# ioboard.net
KiCad netlist of a schematic drawn in EAGLE
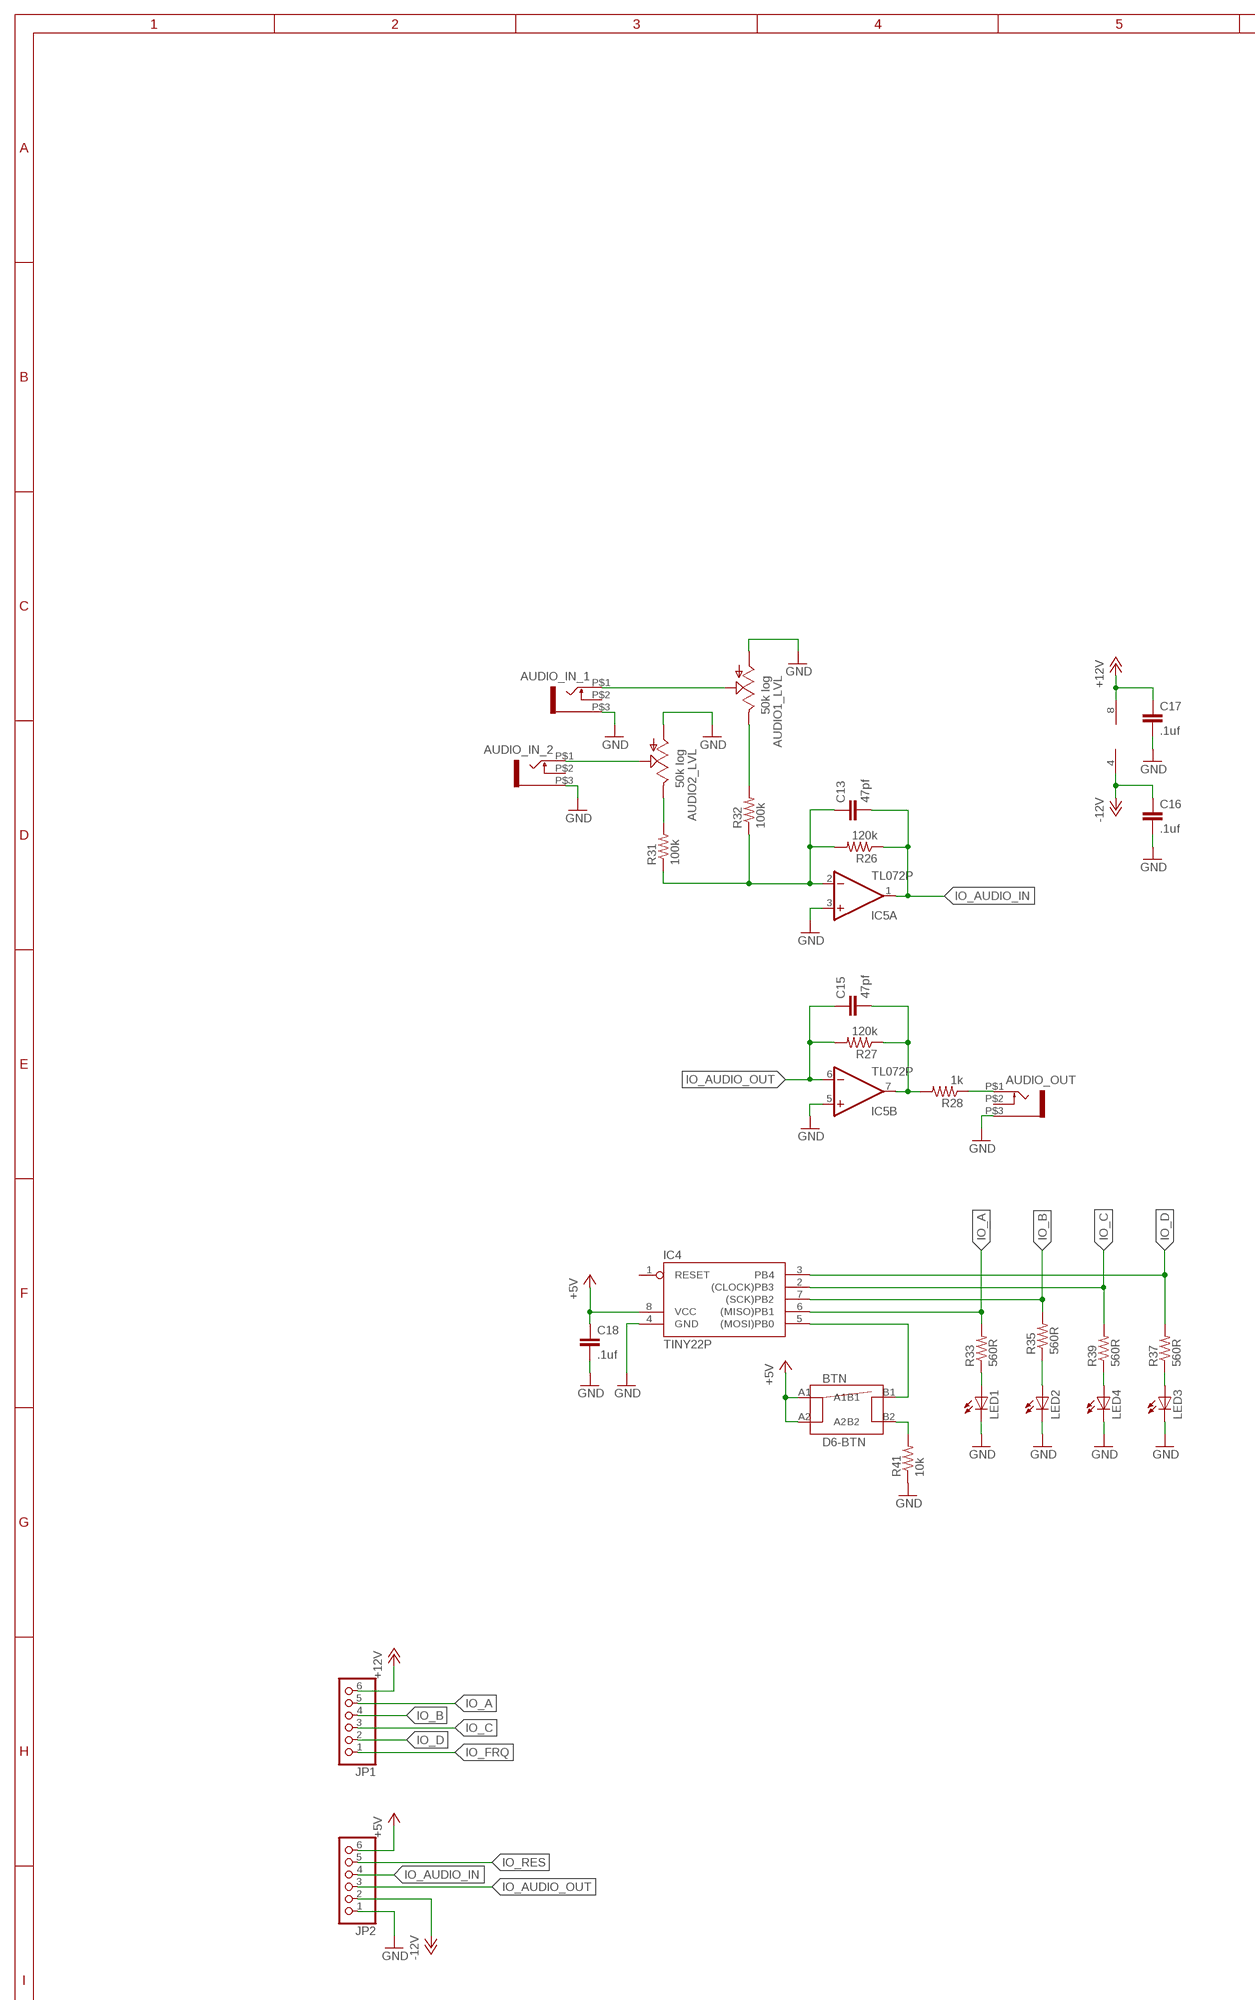
[diagram p0: schematic, sheet 1, part 1 of 2]
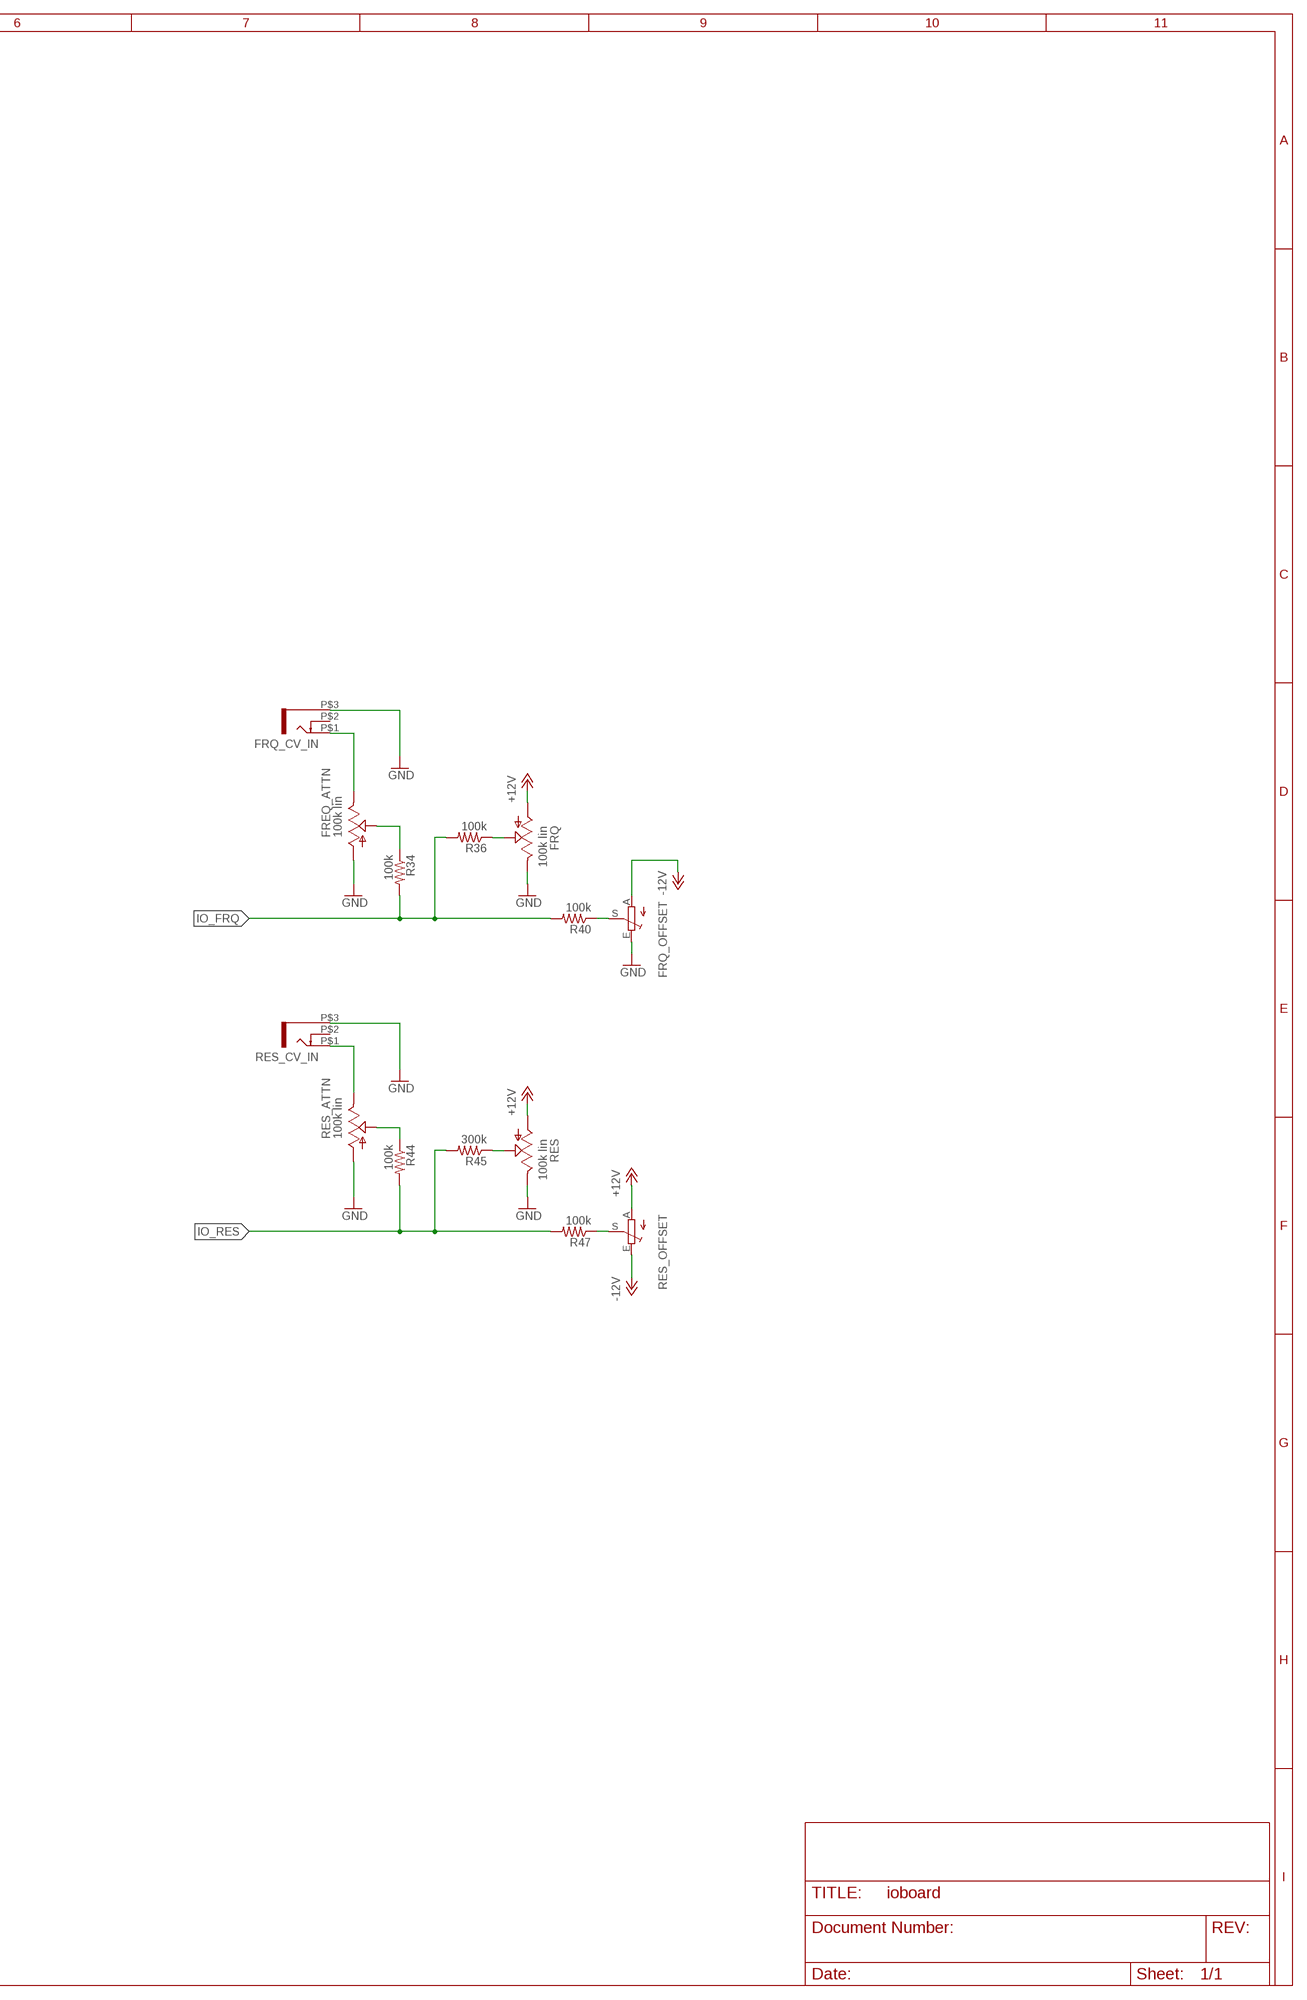
[diagram p1: schematic, sheet 1, part 2 of 2]

(export (version "E")
  (design (tool "Eeschema 10.0.6"))
  (components
    (comp (ref "AUDIO1_LVL")
      (value "50k log")
      (footprint "eagle-import:EVUF")
      (libsource (lib "eagle-import") (part "ALPHA-9MMA"))
    )
    (comp (ref "AUDIO2_LVL")
      (value "50k log")
      (footprint "eagle-import:EVUF")
      (libsource (lib "eagle-import") (part "ALPHA-9MMA"))
    )
    (comp (ref "AUDIO_IN_1")
      (value "WQP-PJ301M-12_JACK")
      (footprint "eagle-import:WQP-PJ301M-12_JACK")
      (libsource (lib "eagle-import") (part "WQP-PJ301M-12_JACK"))
    )
    (comp (ref "AUDIO_IN_2")
      (value "WQP-PJ301M-12_JACK")
      (footprint "eagle-import:WQP-PJ301M-12_JACK")
      (libsource (lib "eagle-import") (part "WQP-PJ301M-12_JACK"))
    )
    (comp (ref "AUDIO_OUT")
      (value "WQP-PJ301M-12_JACK")
      (footprint "eagle-import:WQP-PJ301M-12_JACK")
      (libsource (lib "eagle-import") (part "WQP-PJ301M-12_JACK"))
    )
    (comp (ref "BTN")
      (value "D6-BTN")
      (footprint "eagle-import:D6-BTN")
      (libsource (lib "eagle-import") (part "D6-BTN"))
    )
    (comp (ref "C13")
      (value "47pf")
      (footprint "eagle-import:C050-024X044")
      (libsource (lib "eagle-import") (part "C-EU050-024X044"))
    )
    (comp (ref "C15")
      (value "47pf")
      (footprint "eagle-import:C050-024X044")
      (libsource (lib "eagle-import") (part "C-EU050-024X044"))
    )
    (comp (ref "C16")
      (value ".1uf")
      (footprint "eagle-import:C050-024X044")
      (libsource (lib "eagle-import") (part "C-EU050-024X044"))
    )
    (comp (ref "C17")
      (value ".1uf")
      (footprint "eagle-import:C050-024X044")
      (libsource (lib "eagle-import") (part "C-EU050-024X044"))
    )
    (comp (ref "C18")
      (value ".1uf")
      (footprint "eagle-import:C050-024X044")
      (libsource (lib "eagle-import") (part "C-EU050-024X044"))
    )
    (comp (ref "FREQ_ATTN")
      (value "100k lin")
      (footprint "eagle-import:EVUF")
      (libsource (lib "eagle-import") (part "ALPHA-9MMA"))
    )
    (comp (ref "FRQ")
      (value "100k lin")
      (footprint "eagle-import:EVUF")
      (libsource (lib "eagle-import") (part "ALPHA-9MMA"))
    )
    (comp (ref "FRQ_CV_IN")
      (value "WQP-PJ301M-12_JACK")
      (footprint "eagle-import:WQP-PJ301M-12_JACK")
      (libsource (lib "eagle-import") (part "WQP-PJ301M-12_JACK"))
    )
    (comp (ref "FRQ_OFFSET")
      (value "TRIM_EU-B25P")
      (footprint "eagle-import:B25P")
      (libsource (lib "eagle-import") (part "TRIM_EU-B25P"))
    )
    (comp (ref "IC4")
      (value "TINY22P")
      (footprint "eagle-import:DIL08")
      (libsource (lib "eagle-import") (part "TINY22P"))
    )
    (comp (ref "IC5")
      (value "TL072P")
      (footprint "eagle-import:DIL08")
      (libsource (lib "eagle-import") (part "TL072P"))
    )
    (comp (ref "JP1")
      (value "PINHD-1X6")
      (footprint "eagle-import:1X06")
      (libsource (lib "eagle-import") (part "PINHD-1X6"))
    )
    (comp (ref "JP2")
      (value "PINHD-1X6")
      (footprint "eagle-import:1X06")
      (libsource (lib "eagle-import") (part "PINHD-1X6"))
    )
    (comp (ref "LED1")
      (value "LED3MM")
      (footprint "eagle-import:LED3MM")
      (libsource (lib "eagle-import") (part "LED3MM"))
    )
    (comp (ref "LED2")
      (value "LED3MM")
      (footprint "eagle-import:LED3MM")
      (libsource (lib "eagle-import") (part "LED3MM"))
    )
    (comp (ref "LED3")
      (value "LED3MM")
      (footprint "eagle-import:LED3MM")
      (libsource (lib "eagle-import") (part "LED3MM"))
    )
    (comp (ref "LED4")
      (value "LED3MM")
      (footprint "eagle-import:LED3MM")
      (libsource (lib "eagle-import") (part "LED3MM"))
    )
    (comp (ref "R26")
      (value "120k")
      (footprint "eagle-import:0207_7")
      (libsource (lib "eagle-import") (part "R-US_0207/7"))
    )
    (comp (ref "R27")
      (value "120k")
      (footprint "eagle-import:0207_7")
      (libsource (lib "eagle-import") (part "R-US_0207/7"))
    )
    (comp (ref "R28")
      (value "1k")
      (footprint "eagle-import:0207_7")
      (libsource (lib "eagle-import") (part "R-US_0207/7"))
    )
    (comp (ref "R31")
      (value "100k")
      (footprint "eagle-import:0207_7")
      (libsource (lib "eagle-import") (part "R-US_0207/7"))
    )
    (comp (ref "R32")
      (value "100k")
      (footprint "eagle-import:0207_7")
      (libsource (lib "eagle-import") (part "R-US_0207/7"))
    )
    (comp (ref "R33")
      (value "560R")
      (footprint "eagle-import:0207_7")
      (libsource (lib "eagle-import") (part "R-US_0207/7"))
    )
    (comp (ref "R34")
      (value "100k")
      (footprint "eagle-import:0207_7")
      (libsource (lib "eagle-import") (part "R-US_0207/7"))
    )
    (comp (ref "R35")
      (value "560R")
      (footprint "eagle-import:0207_7")
      (libsource (lib "eagle-import") (part "R-US_0207/7"))
    )
    (comp (ref "R36")
      (value "100k")
      (footprint "eagle-import:0207_7")
      (libsource (lib "eagle-import") (part "R-US_0207/7"))
    )
    (comp (ref "R37")
      (value "560R")
      (footprint "eagle-import:0207_7")
      (libsource (lib "eagle-import") (part "R-US_0207/7"))
    )
    (comp (ref "R39")
      (value "560R")
      (footprint "eagle-import:0207_7")
      (libsource (lib "eagle-import") (part "R-US_0207/7"))
    )
    (comp (ref "R40")
      (value "100k")
      (footprint "eagle-import:0207_7")
      (libsource (lib "eagle-import") (part "R-US_0207/7"))
    )
    (comp (ref "R41")
      (value "10k")
      (footprint "eagle-import:0207_7")
      (libsource (lib "eagle-import") (part "R-US_0207/7"))
    )
    (comp (ref "R44")
      (value "100k")
      (footprint "eagle-import:0207_7")
      (libsource (lib "eagle-import") (part "R-US_0207/7"))
    )
    (comp (ref "R45")
      (value "300k")
      (footprint "eagle-import:0207_7")
      (libsource (lib "eagle-import") (part "R-US_0207/7"))
    )
    (comp (ref "R47")
      (value "100k")
      (footprint "eagle-import:0207_7")
      (libsource (lib "eagle-import") (part "R-US_0207/7"))
    )
    (comp (ref "RES")
      (value "100k lin")
      (footprint "eagle-import:EVUF")
      (libsource (lib "eagle-import") (part "ALPHA-9MMA"))
    )
    (comp (ref "RES_ATTN")
      (value "100k lin")
      (footprint "eagle-import:EVUF")
      (libsource (lib "eagle-import") (part "ALPHA-9MMA"))
    )
    (comp (ref "RES_CV_IN")
      (value "WQP-PJ301M-12_JACK")
      (footprint "eagle-import:WQP-PJ301M-12_JACK")
      (libsource (lib "eagle-import") (part "WQP-PJ301M-12_JACK"))
    )
    (comp (ref "RES_OFFSET")
      (value "TRIM_EU-B25P")
      (footprint "eagle-import:B25P")
      (libsource (lib "eagle-import") (part "TRIM_EU-B25P"))
    )
  )
  (nets
    (net (code "1") (name "+5V") (class "Default")
      (node (ref "BTN") (pin "A1") (pinfunction "A1_A1") (pintype "bidirectional"))
      (node (ref "BTN") (pin "A2") (pinfunction "A2_A2") (pintype "bidirectional"))
      (node (ref "C18") (pin "1") (pinfunction "1_1") (pintype "passive"))
      (node (ref "IC4") (pin "8") (pinfunction "VCC_8") (pintype "power_in"))
      (node (ref "JP2") (pin "6") (pinfunction "6_6") (pintype "passive"))
    )
    (net (code "2") (name "+12V") (class "Default")
      (node (ref "C17") (pin "1") (pinfunction "1_1") (pintype "passive"))
      (node (ref "FRQ") (pin "1") (pinfunction "A_1") (pintype "passive"))
      (node (ref "IC5") (pin "8") (pinfunction "V+_8") (pintype "power_in"))
      (node (ref "JP1") (pin "6") (pinfunction "6_6") (pintype "passive"))
      (node (ref "RES") (pin "1") (pinfunction "A_1") (pintype "passive"))
      (node (ref "RES_OFFSET") (pin "A") (pinfunction "A_A") (pintype "passive"))
    )
    (net (code "3") (name "-12V") (class "Default")
      (node (ref "C16") (pin "1") (pinfunction "1_1") (pintype "passive"))
      (node (ref "FRQ_OFFSET") (pin "A") (pinfunction "A_A") (pintype "passive"))
      (node (ref "IC5") (pin "4") (pinfunction "V-_4") (pintype "power_in"))
      (node (ref "JP2") (pin "2") (pinfunction "2_2") (pintype "passive"))
      (node (ref "RES_OFFSET") (pin "E") (pinfunction "E_E") (pintype "passive"))
    )
    (net (code "4") (name "GND") (class "Default")
      (node (ref "AUDIO1_LVL") (pin "1") (pinfunction "A_1") (pintype "passive"))
      (node (ref "AUDIO2_LVL") (pin "1") (pinfunction "A_1") (pintype "passive"))
      (node (ref "AUDIO_IN_1") (pin "P$3") (pinfunction "1_P$3") (pintype "passive"))
      (node (ref "AUDIO_IN_2") (pin "P$3") (pinfunction "1_P$3") (pintype "passive"))
      (node (ref "AUDIO_OUT") (pin "P$3") (pinfunction "1_P$3") (pintype "passive"))
      (node (ref "C16") (pin "2") (pinfunction "2_2") (pintype "passive"))
      (node (ref "C17") (pin "2") (pinfunction "2_2") (pintype "passive"))
      (node (ref "C18") (pin "2") (pinfunction "2_2") (pintype "passive"))
      (node (ref "FREQ_ATTN") (pin "1") (pinfunction "A_1") (pintype "passive"))
      (node (ref "FRQ") (pin "3") (pinfunction "E_3") (pintype "passive"))
      (node (ref "FRQ_CV_IN") (pin "P$3") (pinfunction "1_P$3") (pintype "passive"))
      (node (ref "FRQ_OFFSET") (pin "E") (pinfunction "E_E") (pintype "passive"))
      (node (ref "IC4") (pin "4") (pinfunction "GND_4") (pintype "power_in"))
      (node (ref "IC5") (pin "3") (pinfunction "+IN_3") (pintype "input"))
      (node (ref "IC5") (pin "5") (pinfunction "+IN_5") (pintype "input"))
      (node (ref "JP2") (pin "1") (pinfunction "1_1") (pintype "passive"))
      (node (ref "LED1") (pin "K") (pinfunction "C_K") (pintype "passive"))
      (node (ref "LED2") (pin "K") (pinfunction "C_K") (pintype "passive"))
      (node (ref "LED3") (pin "K") (pinfunction "C_K") (pintype "passive"))
      (node (ref "LED4") (pin "K") (pinfunction "C_K") (pintype "passive"))
      (node (ref "R41") (pin "1") (pinfunction "1_1") (pintype "passive"))
      (node (ref "RES") (pin "3") (pinfunction "E_3") (pintype "passive"))
      (node (ref "RES_ATTN") (pin "1") (pinfunction "A_1") (pintype "passive"))
      (node (ref "RES_CV_IN") (pin "P$3") (pinfunction "1_P$3") (pintype "passive"))
    )
    (net (code "5") (name "IO_A") (class "Default")
      (node (ref "IC4") (pin "6") (pinfunction "(MISO)PB1_6") (pintype "bidirectional"))
      (node (ref "JP1") (pin "5") (pinfunction "5_5") (pintype "passive"))
      (node (ref "R33") (pin "2") (pinfunction "2_2") (pintype "passive"))
    )
    (net (code "6") (name "IO_AUDIO_IN") (class "Default")
      (node (ref "C13") (pin "2") (pinfunction "2_2") (pintype "passive"))
      (node (ref "IC5") (pin "1") (pinfunction "OUT_1") (pintype "output"))
      (node (ref "JP2") (pin "4") (pinfunction "4_4") (pintype "passive"))
      (node (ref "R26") (pin "1") (pinfunction "1_1") (pintype "passive"))
    )
    (net (code "7") (name "IO_AUDIO_OUT") (class "Default")
      (node (ref "C15") (pin "1") (pinfunction "1_1") (pintype "passive"))
      (node (ref "IC5") (pin "6") (pinfunction "-IN_6") (pintype "input"))
      (node (ref "JP2") (pin "3") (pinfunction "3_3") (pintype "passive"))
      (node (ref "R27") (pin "2") (pinfunction "2_2") (pintype "passive"))
    )
    (net (code "8") (name "IO_B") (class "Default")
      (node (ref "IC4") (pin "7") (pinfunction "(SCK)PB2_7") (pintype "bidirectional"))
      (node (ref "JP1") (pin "4") (pinfunction "4_4") (pintype "passive"))
      (node (ref "R35") (pin "2") (pinfunction "2_2") (pintype "passive"))
    )
    (net (code "9") (name "IO_C") (class "Default")
      (node (ref "IC4") (pin "2") (pinfunction "(CLOCK)PB3_2") (pintype "bidirectional"))
      (node (ref "JP1") (pin "3") (pinfunction "3_3") (pintype "passive"))
      (node (ref "R39") (pin "2") (pinfunction "2_2") (pintype "passive"))
    )
    (net (code "10") (name "IO_D") (class "Default")
      (node (ref "IC4") (pin "3") (pinfunction "PB4_3") (pintype "bidirectional"))
      (node (ref "JP1") (pin "2") (pinfunction "2_2") (pintype "passive"))
      (node (ref "R37") (pin "2") (pinfunction "2_2") (pintype "passive"))
    )
    (net (code "11") (name "IO_FRQ") (class "Default")
      (node (ref "JP1") (pin "1") (pinfunction "1_1") (pintype "passive"))
      (node (ref "R34") (pin "2") (pinfunction "2_2") (pintype "passive"))
      (node (ref "R36") (pin "2") (pinfunction "2_2") (pintype "passive"))
      (node (ref "R40") (pin "2") (pinfunction "2_2") (pintype "passive"))
    )
    (net (code "12") (name "IO_RES") (class "Default")
      (node (ref "JP2") (pin "5") (pinfunction "5_5") (pintype "passive"))
      (node (ref "R44") (pin "2") (pinfunction "2_2") (pintype "passive"))
      (node (ref "R45") (pin "2") (pinfunction "2_2") (pintype "passive"))
      (node (ref "R47") (pin "2") (pinfunction "2_2") (pintype "passive"))
    )
    (net (code "13") (name "Net-(AUDIO1_LVL-E)") (class "Default")
      (node (ref "AUDIO1_LVL") (pin "3") (pinfunction "E_3") (pintype "passive"))
      (node (ref "R32") (pin "2") (pinfunction "2_2") (pintype "passive"))
    )
    (net (code "14") (name "Net-(AUDIO1_LVL-S)") (class "Default")
      (node (ref "AUDIO1_LVL") (pin "2") (pinfunction "S_2") (pintype "passive"))
      (node (ref "AUDIO_IN_1") (pin "P$1") (pinfunction "2_P$1") (pintype "passive"))
    )
    (net (code "15") (name "Net-(AUDIO2_LVL-E)") (class "Default")
      (node (ref "AUDIO2_LVL") (pin "3") (pinfunction "E_3") (pintype "passive"))
      (node (ref "R31") (pin "2") (pinfunction "2_2") (pintype "passive"))
    )
    (net (code "16") (name "Net-(AUDIO2_LVL-S)") (class "Default")
      (node (ref "AUDIO2_LVL") (pin "2") (pinfunction "S_2") (pintype "passive"))
      (node (ref "AUDIO_IN_2") (pin "P$1") (pinfunction "2_P$1") (pintype "passive"))
    )
    (net (code "17") (name "Net-(AUDIO_OUT-2)") (class "Default")
      (node (ref "AUDIO_OUT") (pin "P$1") (pinfunction "2_P$1") (pintype "passive"))
      (node (ref "R28") (pin "1") (pinfunction "1_1") (pintype "passive"))
    )
    (net (code "18") (name "Net-(BTN-PadB2)") (class "Default")
      (node (ref "BTN") (pin "B2") (pinfunction "B2_B2") (pintype "bidirectional"))
      (node (ref "R41") (pin "2") (pinfunction "2_2") (pintype "passive"))
    )
    (net (code "19") (name "Net-(FREQ_ATTN-E)") (class "Default")
      (node (ref "FREQ_ATTN") (pin "3") (pinfunction "E_3") (pintype "passive"))
      (node (ref "FRQ_CV_IN") (pin "P$1") (pinfunction "2_P$1") (pintype "passive"))
    )
    (net (code "20") (name "Net-(FREQ_ATTN-S)") (class "Default")
      (node (ref "FREQ_ATTN") (pin "2") (pinfunction "S_2") (pintype "passive"))
      (node (ref "R34") (pin "1") (pinfunction "1_1") (pintype "passive"))
    )
    (net (code "21") (name "Net-(FRQ-S)") (class "Default")
      (node (ref "FRQ") (pin "2") (pinfunction "S_2") (pintype "passive"))
      (node (ref "R36") (pin "1") (pinfunction "1_1") (pintype "passive"))
    )
    (net (code "22") (name "Net-(FRQ_OFFSET-PadS)") (class "Default")
      (node (ref "FRQ_OFFSET") (pin "S") (pinfunction "S_S") (pintype "passive"))
      (node (ref "R40") (pin "1") (pinfunction "1_1") (pintype "passive"))
    )
    (net (code "23") (name "Net-(IC4-(MOSI)PB0)") (class "Default")
      (node (ref "BTN") (pin "B1") (pinfunction "B1_B1") (pintype "bidirectional"))
      (node (ref "IC4") (pin "5") (pinfunction "(MOSI)PB0_5") (pintype "bidirectional"))
    )
    (net (code "24") (name "Net-(IC5A--IN)") (class "Default")
      (node (ref "C13") (pin "1") (pinfunction "1_1") (pintype "passive"))
      (node (ref "IC5") (pin "2") (pinfunction "-IN_2") (pintype "input"))
      (node (ref "R26") (pin "2") (pinfunction "2_2") (pintype "passive"))
      (node (ref "R31") (pin "1") (pinfunction "1_1") (pintype "passive"))
      (node (ref "R32") (pin "1") (pinfunction "1_1") (pintype "passive"))
    )
    (net (code "25") (name "Net-(IC5B-OUT)") (class "Default")
      (node (ref "C15") (pin "2") (pinfunction "2_2") (pintype "passive"))
      (node (ref "IC5") (pin "7") (pinfunction "OUT_7") (pintype "output"))
      (node (ref "R27") (pin "1") (pinfunction "1_1") (pintype "passive"))
      (node (ref "R28") (pin "2") (pinfunction "2_2") (pintype "passive"))
    )
    (net (code "26") (name "Net-(LED1-PadA)") (class "Default")
      (node (ref "LED1") (pin "A") (pinfunction "A_A") (pintype "passive"))
      (node (ref "R33") (pin "1") (pinfunction "1_1") (pintype "passive"))
    )
    (net (code "27") (name "Net-(LED2-PadA)") (class "Default")
      (node (ref "LED2") (pin "A") (pinfunction "A_A") (pintype "passive"))
      (node (ref "R35") (pin "1") (pinfunction "1_1") (pintype "passive"))
    )
    (net (code "28") (name "Net-(LED3-PadA)") (class "Default")
      (node (ref "LED3") (pin "A") (pinfunction "A_A") (pintype "passive"))
      (node (ref "R37") (pin "1") (pinfunction "1_1") (pintype "passive"))
    )
    (net (code "29") (name "Net-(LED4-PadA)") (class "Default")
      (node (ref "LED4") (pin "A") (pinfunction "A_A") (pintype "passive"))
      (node (ref "R39") (pin "1") (pinfunction "1_1") (pintype "passive"))
    )
    (net (code "30") (name "Net-(R47-Pad1)") (class "Default")
      (node (ref "R47") (pin "1") (pinfunction "1_1") (pintype "passive"))
      (node (ref "RES_OFFSET") (pin "S") (pinfunction "S_S") (pintype "passive"))
    )
    (net (code "31") (name "Net-(RES-S)") (class "Default")
      (node (ref "R45") (pin "1") (pinfunction "1_1") (pintype "passive"))
      (node (ref "RES") (pin "2") (pinfunction "S_2") (pintype "passive"))
    )
    (net (code "32") (name "Net-(RES_ATTN-E)") (class "Default")
      (node (ref "RES_ATTN") (pin "3") (pinfunction "E_3") (pintype "passive"))
      (node (ref "RES_CV_IN") (pin "P$1") (pinfunction "2_P$1") (pintype "passive"))
    )
    (net (code "33") (name "Net-(RES_ATTN-S)") (class "Default")
      (node (ref "R44") (pin "1") (pinfunction "1_1") (pintype "passive"))
      (node (ref "RES_ATTN") (pin "2") (pinfunction "S_2") (pintype "passive"))
    )
    (net (code "34") (name "unconnected-(AUDIO_IN_1-3-PadP$2)") (class "Default")
      (node (ref "AUDIO_IN_1") (pin "P$2") (pinfunction "3_P$2") (pintype "passive"))
    )
    (net (code "35") (name "unconnected-(AUDIO_IN_2-3-PadP$2)") (class "Default")
      (node (ref "AUDIO_IN_2") (pin "P$2") (pinfunction "3_P$2") (pintype "passive"))
    )
    (net (code "36") (name "unconnected-(AUDIO_OUT-3-PadP$2)") (class "Default")
      (node (ref "AUDIO_OUT") (pin "P$2") (pinfunction "3_P$2") (pintype "passive"))
    )
    (net (code "37") (name "unconnected-(FRQ_CV_IN-3-PadP$2)") (class "Default")
      (node (ref "FRQ_CV_IN") (pin "P$2") (pinfunction "3_P$2") (pintype "passive"))
    )
    (net (code "38") (name "unconnected-(IC4-RESET-Pad1)") (class "Default")
      (node (ref "IC4") (pin "1") (pinfunction "RESET_1") (pintype "input"))
    )
    (net (code "39") (name "unconnected-(RES_CV_IN-3-PadP$2)") (class "Default")
      (node (ref "RES_CV_IN") (pin "P$2") (pinfunction "3_P$2") (pintype "passive"))
    )
  )
)
